# Sheet1.net
KiCad netlist of a schematic drawn in Altium Designer
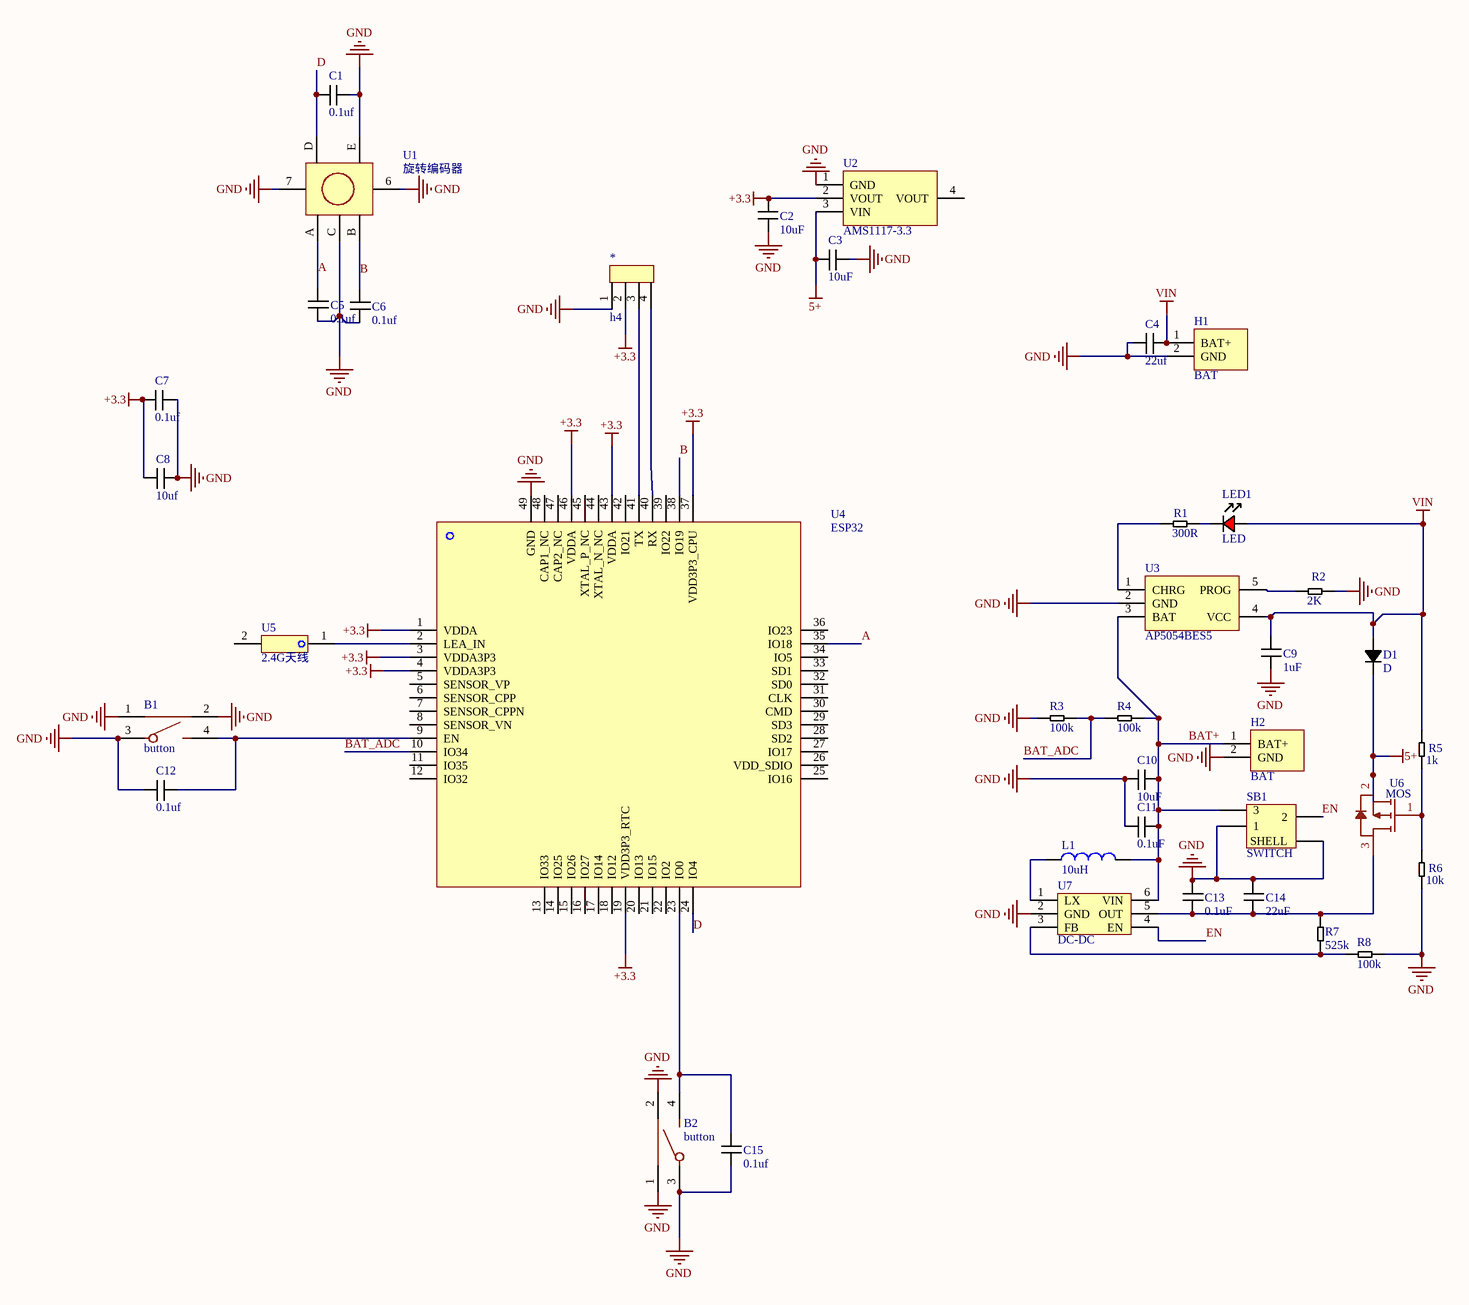
[diagram p0: Sheet1.SchDoc]

(export (version "E")
  (design (tool "Eeschema 10.0.6"))
  (components
    (comp (ref "*") (value "h4") (footprint "pin4") (libsource (lib "Schlib1") (part "h4")))
    (comp (ref "B1") (value "button") (footprint "button") (libsource (lib "Schlib1") (part "button")))
    (comp (ref "B2") (value "button") (footprint "button") (libsource (lib "Schlib1") (part "button")))
    (comp (ref "C1") (value "0.1uf") (footprint "0805CAP") (libsource (lib "Schlib1") (part "CAP")))
    (comp (ref "C2") (value "10uF") (footprint "0805CAP") (libsource (lib "Schlib1") (part "CAP")))
    (comp (ref "C3") (value "10uF") (footprint "0805CAP") (libsource (lib "Schlib1") (part "CAP")))
    (comp (ref "C4") (value "22uf") (footprint "0805CAP") (libsource (lib "Schlib1") (part "CAP")))
    (comp (ref "C5") (value "0.1uf") (footprint "0805CAP") (libsource (lib "Schlib1") (part "CAP")))
    (comp (ref "C6") (value "0.1uf") (footprint "0805CAP") (libsource (lib "Schlib1") (part "CAP")))
    (comp (ref "C7") (value "0.1uf") (footprint "0805CAP") (libsource (lib "Schlib1") (part "CAP")))
    (comp (ref "C8") (value "10uf") (footprint "0805CAP") (libsource (lib "Schlib1") (part "CAP")))
    (comp (ref "C9") (value "1uF") (footprint "0805CAP") (libsource (lib "Schlib1") (part "CAP")))
    (comp (ref "C10") (value "10uF") (footprint "0805CAP") (libsource (lib "Schlib1") (part "CAP")))
    (comp (ref "C11") (value "0.1uF") (footprint "0805CAP") (libsource (lib "Schlib1") (part "CAP")))
    (comp (ref "C12") (value "0.1uf") (footprint "0805CAP") (libsource (lib "Schlib1") (part "CAP")))
    (comp (ref "C13") (value "0.1uF") (footprint "0805CAP") (libsource (lib "Schlib1") (part "CAP")))
    (comp (ref "C14") (value "22uF") (footprint "0805CAP") (libsource (lib "Schlib1") (part "CAP")))
    (comp (ref "C15") (value "0.1uf") (footprint "0805CAP") (libsource (lib "Schlib1") (part "CAP")))
    (comp (ref "D1") (value "D") (footprint "1206D") (libsource (lib "Schlib1") (part "D")))
    (comp (ref "H1") (value "BAT") (footprint "BAT") (libsource (lib "Schlib1") (part "BAT")))
    (comp (ref "H2") (value "BAT") (footprint "BAT") (libsource (lib "Schlib1") (part "BAT")))
    (comp (ref "L1") (value "10uH") (footprint "LND") (libsource (lib "Schlib1") (part "LND")))
    (comp (ref "LED1") (value "LED") (footprint "0805LED") (libsource (lib "Schlib1") (part "LED")))
    (comp (ref "R1") (value "300R") (footprint "0805R") (libsource (lib "Schlib1") (part "RES")))
    (comp (ref "R2") (value "2K") (footprint "0805R") (libsource (lib "Schlib1") (part "RES")))
    (comp (ref "R3") (value "100k") (footprint "0805R") (libsource (lib "Schlib1") (part "RES")))
    (comp (ref "R4") (value "100k") (footprint "0805R") (libsource (lib "Schlib1") (part "RES")))
    (comp (ref "R5") (value "1k") (footprint "0805R") (libsource (lib "Schlib1") (part "RES")))
    (comp (ref "R6") (value "10k") (footprint "0805R") (libsource (lib "Schlib1") (part "RES")))
    (comp (ref "R7") (value "525k") (footprint "0805R") (libsource (lib "Schlib1") (part "RES")))
    (comp (ref "R8") (value "100k") (footprint "0805R") (libsource (lib "Schlib1") (part "RES")))
    (comp (ref "SB1") (value "SWITCH") (footprint "SB") (libsource (lib "Schlib1") (part "SWITCH")))
    (comp (ref "U1")
      (value "旋转编码器")
      (footprint "SW-TH_EC11XXXXXXXX")
      (libsource (lib "Schlib1") (part "旋转编码器"))
    )
    (comp (ref "U2")
      (value "AMS1117-3.3")
      (footprint "AMS1117-3.3")
      (libsource (lib "Schlib1") (part "AMS1117-3.3"))
    )
    (comp (ref "U3")
      (value "AP5054BES5")
      (footprint "AP5054BES5")
      (libsource (lib "Schlib1") (part "AP5054BES5"))
    )
    (comp (ref "U4")
      (value "ESP32")
      (footprint "ESP32_PICO")
      (libsource (lib "Schlib1") (part "ESP32-PICO-D4"))
    )
    (comp (ref "U5") (value "2.4G天线") (footprint "2.4G天线") (libsource (lib "Schlib1") (part "2.4G天线")))
    (comp (ref "U6") (value "MOS") (footprint "PMOS") (libsource (lib "Schlib1") (part "PMOS")))
    (comp (ref "U7")
      (value "DC-DC")
      (footprint "FP6715S6CTR")
      (libsource (lib "Schlib1") (part "FP6715S6CTR"))
    )
  )
  (nets
    (net (code "1") (name "+3.3") (class "Default")
      (node (ref "*") (pin "2") (pintype "passive"))
      (node (ref "C2") (pin "1") (pinfunction "SHELL_1") (pintype "passive"))
      (node (ref "C7") (pin "1") (pinfunction "SHELL_1") (pintype "passive"))
      (node (ref "C8") (pin "1") (pinfunction "SHELL_1") (pintype "passive"))
      (node (ref "U2") (pin "2") (pinfunction "VOUT_2") (pintype "passive"))
      (node (ref "U4") (pin "1") (pinfunction "VDDA_1") (pintype "passive"))
      (node (ref "U4") (pin "19") (pinfunction "VDD3P3_RTC_19") (pintype "passive"))
      (node (ref "U4") (pin "3") (pinfunction "VDDA3P3_3") (pintype "passive"))
      (node (ref "U4") (pin "37") (pinfunction "VDD3P3_CPU_37") (pintype "passive"))
      (node (ref "U4") (pin "4") (pinfunction "VDDA3P3_4") (pintype "passive"))
      (node (ref "U4") (pin "43") (pinfunction "VDDA_43") (pintype "passive"))
      (node (ref "U4") (pin "46") (pinfunction "VDDA_46") (pintype "passive"))
    )
    (net (code "2") (name "/A") (class "Default")
      (node (ref "C5") (pin "2") (pinfunction "SHELL_2") (pintype "passive"))
      (node (ref "U1") (pin "A") (pintype "passive"))
      (node (ref "U4") (pin "35") (pinfunction "IO18_35") (pintype "passive"))
    )
    (net (code "3") (name "/B") (class "Default")
      (node (ref "C6") (pin "2") (pinfunction "SHELL_2") (pintype "passive"))
      (node (ref "U1") (pin "B") (pintype "passive"))
      (node (ref "U4") (pin "38") (pinfunction "IO19_38") (pintype "passive"))
    )
    (net (code "4") (name "/BAT+") (class "Default")
      (node (ref "C10") (pin "2") (pinfunction "SHELL_2") (pintype "passive"))
      (node (ref "C11") (pin "2") (pinfunction "SHELL_2") (pintype "passive"))
      (node (ref "H2") (pin "1") (pinfunction "BAT+_1") (pintype "passive"))
      (node (ref "L1") (pin "2") (pintype "passive"))
      (node (ref "R4") (pin "2") (pinfunction "2_2") (pintype "passive"))
      (node (ref "SB1") (pin "3") (pinfunction "3_3") (pintype "passive"))
      (node (ref "U3") (pin "3") (pinfunction "BAT_3") (pintype "passive"))
      (node (ref "U7") (pin "6") (pinfunction "VIN_6") (pintype "passive"))
    )
    (net (code "5") (name "/BAT_ADC") (class "Default")
      (node (ref "R3") (pin "2") (pinfunction "2_2") (pintype "passive"))
      (node (ref "R4") (pin "1") (pinfunction "1_1") (pintype "passive"))
      (node (ref "U4") (pin "10") (pinfunction "IO34_10") (pintype "passive"))
    )
    (net (code "6") (name "/D") (class "Default")
      (node (ref "C1") (pin "1") (pinfunction "SHELL_1") (pintype "passive"))
      (node (ref "U1") (pin "D") (pintype "passive"))
      (node (ref "U4") (pin "24") (pinfunction "IO4_24") (pintype "passive"))
    )
    (net (code "7") (name "/EN") (class "Default")
      (node (ref "SB1") (pin "2") (pinfunction "2_2") (pintype "passive"))
      (node (ref "U7") (pin "4") (pinfunction "EN_4") (pintype "passive"))
    )
    (net (code "8") (name "5+") (class "Default")
      (node (ref "C3") (pin "1") (pinfunction "SHELL_1") (pintype "passive"))
      (node (ref "D1") (pin "2") (pinfunction "-_2") (pintype "passive"))
      (node (ref "U2") (pin "3") (pinfunction "VIN_3") (pintype "passive"))
      (node (ref "U6") (pin "2") (pinfunction "S_2") (pintype "passive"))
    )
    (net (code "9") (name "GND") (class "Default")
      (node (ref "*") (pin "1") (pintype "passive"))
      (node (ref "B1") (pin "1") (pinfunction "H_1") (pintype "passive"))
      (node (ref "B1") (pin "2") (pinfunction "H_2") (pintype "passive"))
      (node (ref "B1") (pin "3") (pinfunction "H_3") (pintype "passive"))
      (node (ref "B2") (pin "1") (pinfunction "H_1") (pintype "passive"))
      (node (ref "B2") (pin "2") (pinfunction "H_2") (pintype "passive"))
      (node (ref "B2") (pin "3") (pinfunction "H_3") (pintype "passive"))
      (node (ref "C1") (pin "2") (pinfunction "SHELL_2") (pintype "passive"))
      (node (ref "C10") (pin "1") (pinfunction "SHELL_1") (pintype "passive"))
      (node (ref "C11") (pin "1") (pinfunction "SHELL_1") (pintype "passive"))
      (node (ref "C12") (pin "1") (pinfunction "SHELL_1") (pintype "passive"))
      (node (ref "C13") (pin "2") (pinfunction "SHELL_2") (pintype "passive"))
      (node (ref "C14") (pin "2") (pinfunction "SHELL_2") (pintype "passive"))
      (node (ref "C15") (pin "1") (pinfunction "SHELL_1") (pintype "passive"))
      (node (ref "C2") (pin "2") (pinfunction "SHELL_2") (pintype "passive"))
      (node (ref "C3") (pin "2") (pinfunction "SHELL_2") (pintype "passive"))
      (node (ref "C4") (pin "1") (pinfunction "SHELL_1") (pintype "passive"))
      (node (ref "C5") (pin "1") (pinfunction "SHELL_1") (pintype "passive"))
      (node (ref "C6") (pin "1") (pinfunction "SHELL_1") (pintype "passive"))
      (node (ref "C7") (pin "2") (pinfunction "SHELL_2") (pintype "passive"))
      (node (ref "C8") (pin "2") (pinfunction "SHELL_2") (pintype "passive"))
      (node (ref "C9") (pin "1") (pinfunction "SHELL_1") (pintype "passive"))
      (node (ref "H1") (pin "2") (pinfunction "GND_2") (pintype "passive"))
      (node (ref "H2") (pin "2") (pinfunction "GND_2") (pintype "passive"))
      (node (ref "R2") (pin "2") (pinfunction "2_2") (pintype "passive"))
      (node (ref "R3") (pin "1") (pinfunction "1_1") (pintype "passive"))
      (node (ref "R6") (pin "1") (pinfunction "1_1") (pintype "passive"))
      (node (ref "R8") (pin "1") (pinfunction "1_1") (pintype "passive"))
      (node (ref "SB1") (pin "1") (pinfunction "1_1") (pintype "passive"))
      (node (ref "SB1") (pin "4") (pinfunction "SHELL_4") (pintype "passive"))
      (node (ref "U1") (pin "6") (pintype "passive"))
      (node (ref "U1") (pin "7") (pintype "passive"))
      (node (ref "U1") (pin "C") (pintype "passive"))
      (node (ref "U1") (pin "E") (pintype "passive"))
      (node (ref "U2") (pin "1") (pinfunction "GND_1") (pintype "passive"))
      (node (ref "U3") (pin "2") (pinfunction "GND_2") (pintype "passive"))
      (node (ref "U4") (pin "49") (pinfunction "GND_49") (pintype "passive"))
      (node (ref "U7") (pin "2") (pinfunction "GND_2") (pintype "passive"))
    )
    (net (code "10") (name "Net-(LED1--)") (class "Default")
      (node (ref "LED1") (pin "2") (pinfunction "-_2") (pintype "passive"))
      (node (ref "R1") (pin "2") (pinfunction "2_2") (pintype "passive"))
    )
    (net (code "11") (name "Net-(U3-CHRG)") (class "Default")
      (node (ref "R1") (pin "1") (pinfunction "1_1") (pintype "passive"))
      (node (ref "U3") (pin "1") (pinfunction "CHRG_1") (pintype "passive"))
    )
    (net (code "12") (name "Net-(U3-PROG)") (class "Default")
      (node (ref "R2") (pin "1") (pinfunction "1_1") (pintype "passive"))
      (node (ref "U3") (pin "5") (pinfunction "PROG_5") (pintype "passive"))
    )
    (net (code "13") (name "Net-(U4-EN)") (class "Default")
      (node (ref "B1") (pin "4") (pinfunction "H_4") (pintype "passive"))
      (node (ref "C12") (pin "2") (pinfunction "SHELL_2") (pintype "passive"))
      (node (ref "U4") (pin "9") (pinfunction "EN_9") (pintype "passive"))
    )
    (net (code "14") (name "Net-(U4-IO0)") (class "Default")
      (node (ref "B2") (pin "4") (pinfunction "H_4") (pintype "passive"))
      (node (ref "C15") (pin "2") (pinfunction "SHELL_2") (pintype "passive"))
      (node (ref "U4") (pin "23") (pinfunction "IO0_23") (pintype "passive"))
    )
    (net (code "15") (name "Net-(U4-LEA_IN)") (class "Default")
      (node (ref "U4") (pin "2") (pinfunction "LEA_IN_2") (pintype "passive"))
      (node (ref "U5") (pin "1") (pintype "passive"))
    )
    (net (code "16") (name "Net-(U4-RX)") (class "Default")
      (node (ref "*") (pin "4") (pintype "passive"))
      (node (ref "U4") (pin "40") (pinfunction "RX_40") (pintype "passive"))
    )
    (net (code "17") (name "Net-(U4-TX)") (class "Default")
      (node (ref "*") (pin "3") (pintype "passive"))
      (node (ref "U4") (pin "41") (pinfunction "TX_41") (pintype "passive"))
    )
    (net (code "18") (name "Net-(U6-D)") (class "Default")
      (node (ref "C13") (pin "1") (pinfunction "SHELL_1") (pintype "passive"))
      (node (ref "C14") (pin "1") (pinfunction "SHELL_1") (pintype "passive"))
      (node (ref "R7") (pin "2") (pinfunction "2_2") (pintype "passive"))
      (node (ref "U6") (pin "3") (pinfunction "D_3") (pintype "passive"))
      (node (ref "U7") (pin "5") (pinfunction "OUT_5") (pintype "passive"))
    )
    (net (code "19") (name "Net-(U6-G)") (class "Default")
      (node (ref "R5") (pin "1") (pinfunction "1_1") (pintype "passive"))
      (node (ref "R6") (pin "2") (pinfunction "2_2") (pintype "passive"))
      (node (ref "U6") (pin "1") (pinfunction "G_1") (pintype "passive"))
    )
    (net (code "20") (name "Net-(U7-FB)") (class "Default")
      (node (ref "R7") (pin "1") (pinfunction "1_1") (pintype "passive"))
      (node (ref "R8") (pin "2") (pinfunction "2_2") (pintype "passive"))
      (node (ref "U7") (pin "3") (pinfunction "FB_3") (pintype "passive"))
    )
    (net (code "21") (name "Net-(U7-LX)") (class "Default")
      (node (ref "L1") (pin "1") (pintype "passive"))
      (node (ref "U7") (pin "1") (pinfunction "LX_1") (pintype "passive"))
    )
    (net (code "22") (name "VIN") (class "Default")
      (node (ref "C4") (pin "2") (pinfunction "SHELL_2") (pintype "passive"))
      (node (ref "C9") (pin "2") (pinfunction "SHELL_2") (pintype "passive"))
      (node (ref "D1") (pin "1") (pinfunction "+_1") (pintype "passive"))
      (node (ref "H1") (pin "1") (pinfunction "BAT+_1") (pintype "passive"))
      (node (ref "LED1") (pin "1") (pinfunction "+_1") (pintype "passive"))
      (node (ref "R5") (pin "2") (pinfunction "2_2") (pintype "passive"))
      (node (ref "U3") (pin "4") (pinfunction "VCC_4") (pintype "passive"))
    )
    (net (code "23") (name "unconnected-(U2-VOUT-Pad4)") (class "Default")
      (node (ref "U2") (pin "4") (pinfunction "VOUT_4") (pintype "passive"))
    )
    (net (code "24") (name "unconnected-(U4-CAP1_NC-Pad48)") (class "Default")
      (node (ref "U4") (pin "48") (pinfunction "CAP1_NC_48") (pintype "passive"))
    )
    (net (code "25") (name "unconnected-(U4-CAP2_NC-Pad47)") (class "Default")
      (node (ref "U4") (pin "47") (pinfunction "CAP2_NC_47") (pintype "passive"))
    )
    (net (code "26") (name "unconnected-(U4-CLK-Pad31)") (class "Default")
      (node (ref "U4") (pin "31") (pinfunction "CLK_31") (pintype "passive"))
    )
    (net (code "27") (name "unconnected-(U4-CMD-Pad30)") (class "Default")
      (node (ref "U4") (pin "30") (pinfunction "CMD_30") (pintype "passive"))
    )
    (net (code "28") (name "unconnected-(U4-IO2-Pad22)") (class "Default")
      (node (ref "U4") (pin "22") (pinfunction "IO2_22") (pintype "passive"))
    )
    (net (code "29") (name "unconnected-(U4-IO5-Pad34)") (class "Default")
      (node (ref "U4") (pin "34") (pinfunction "IO5_34") (pintype "passive"))
    )
    (net (code "30") (name "unconnected-(U4-IO12-Pad18)") (class "Default")
      (node (ref "U4") (pin "18") (pinfunction "IO12_18") (pintype "passive"))
    )
    (net (code "31") (name "unconnected-(U4-IO13-Pad20)") (class "Default")
      (node (ref "U4") (pin "20") (pinfunction "IO13_20") (pintype "passive"))
    )
    (net (code "32") (name "unconnected-(U4-IO14-Pad17)") (class "Default")
      (node (ref "U4") (pin "17") (pinfunction "IO14_17") (pintype "passive"))
    )
    (net (code "33") (name "unconnected-(U4-IO15-Pad21)") (class "Default")
      (node (ref "U4") (pin "21") (pinfunction "IO15_21") (pintype "passive"))
    )
    (net (code "34") (name "unconnected-(U4-IO16-Pad25)") (class "Default")
      (node (ref "U4") (pin "25") (pinfunction "IO16_25") (pintype "passive"))
    )
    (net (code "35") (name "unconnected-(U4-IO17-Pad27)") (class "Default")
      (node (ref "U4") (pin "27") (pinfunction "IO17_27") (pintype "passive"))
    )
    (net (code "36") (name "unconnected-(U4-IO21-Pad42)") (class "Default")
      (node (ref "U4") (pin "42") (pinfunction "IO21_42") (pintype "passive"))
    )
    (net (code "37") (name "unconnected-(U4-IO22-Pad39)") (class "Default")
      (node (ref "U4") (pin "39") (pinfunction "IO22_39") (pintype "passive"))
    )
    (net (code "38") (name "unconnected-(U4-IO23-Pad36)") (class "Default")
      (node (ref "U4") (pin "36") (pinfunction "IO23_36") (pintype "passive"))
    )
    (net (code "39") (name "unconnected-(U4-IO25-Pad14)") (class "Default")
      (node (ref "U4") (pin "14") (pinfunction "IO25_14") (pintype "passive"))
    )
    (net (code "40") (name "unconnected-(U4-IO26-Pad15)") (class "Default")
      (node (ref "U4") (pin "15") (pinfunction "IO26_15") (pintype "passive"))
    )
    (net (code "41") (name "unconnected-(U4-IO27-Pad16)") (class "Default")
      (node (ref "U4") (pin "16") (pinfunction "IO27_16") (pintype "passive"))
    )
    (net (code "42") (name "unconnected-(U4-IO32-Pad12)") (class "Default")
      (node (ref "U4") (pin "12") (pinfunction "IO32_12") (pintype "passive"))
    )
    (net (code "43") (name "unconnected-(U4-IO33-Pad13)") (class "Default")
      (node (ref "U4") (pin "13") (pinfunction "IO33_13") (pintype "passive"))
    )
    (net (code "44") (name "unconnected-(U4-IO35-Pad11)") (class "Default")
      (node (ref "U4") (pin "11") (pinfunction "IO35_11") (pintype "passive"))
    )
    (net (code "45") (name "unconnected-(U4-SD0-Pad32)") (class "Default")
      (node (ref "U4") (pin "32") (pinfunction "SD0_32") (pintype "passive"))
    )
    (net (code "46") (name "unconnected-(U4-SD1-Pad33)") (class "Default")
      (node (ref "U4") (pin "33") (pinfunction "SD1_33") (pintype "passive"))
    )
    (net (code "47") (name "unconnected-(U4-SD2-Pad28)") (class "Default")
      (node (ref "U4") (pin "28") (pinfunction "SD2_28") (pintype "passive"))
    )
    (net (code "48") (name "unconnected-(U4-SD3-Pad29)") (class "Default")
      (node (ref "U4") (pin "29") (pinfunction "SD3_29") (pintype "passive"))
    )
    (net (code "49") (name "unconnected-(U4-SENSOR_CPP-Pad6)") (class "Default")
      (node (ref "U4") (pin "6") (pinfunction "SENSOR_CPP_6") (pintype "passive"))
    )
    (net (code "50") (name "unconnected-(U4-SENSOR_CPPN-Pad7)") (class "Default")
      (node (ref "U4") (pin "7") (pinfunction "SENSOR_CPPN_7") (pintype "passive"))
    )
    (net (code "51") (name "unconnected-(U4-SENSOR_VN-Pad8)") (class "Default")
      (node (ref "U4") (pin "8") (pinfunction "SENSOR_VN_8") (pintype "passive"))
    )
    (net (code "52") (name "unconnected-(U4-SENSOR_VP-Pad5)") (class "Default")
      (node (ref "U4") (pin "5") (pinfunction "SENSOR_VP_5") (pintype "passive"))
    )
    (net (code "53") (name "unconnected-(U4-VDD_SDIO-Pad26)") (class "Default")
      (node (ref "U4") (pin "26") (pinfunction "VDD_SDIO_26") (pintype "passive"))
    )
    (net (code "54") (name "unconnected-(U4-XTAL_N_NC-Pad44)") (class "Default")
      (node (ref "U4") (pin "44") (pinfunction "XTAL_N_NC_44") (pintype "passive"))
    )
    (net (code "55") (name "unconnected-(U4-XTAL_P_NC-Pad45)") (class "Default")
      (node (ref "U4") (pin "45") (pinfunction "XTAL_P_NC_45") (pintype "passive"))
    )
    (net (code "56") (name "unconnected-(U5-Pad2)") (class "Default")
      (node (ref "U5") (pin "2") (pintype "passive"))
    )
  )
)
